# guitar_tuner_main_board.net
KiCad netlist of a schematic drawn in EAGLE
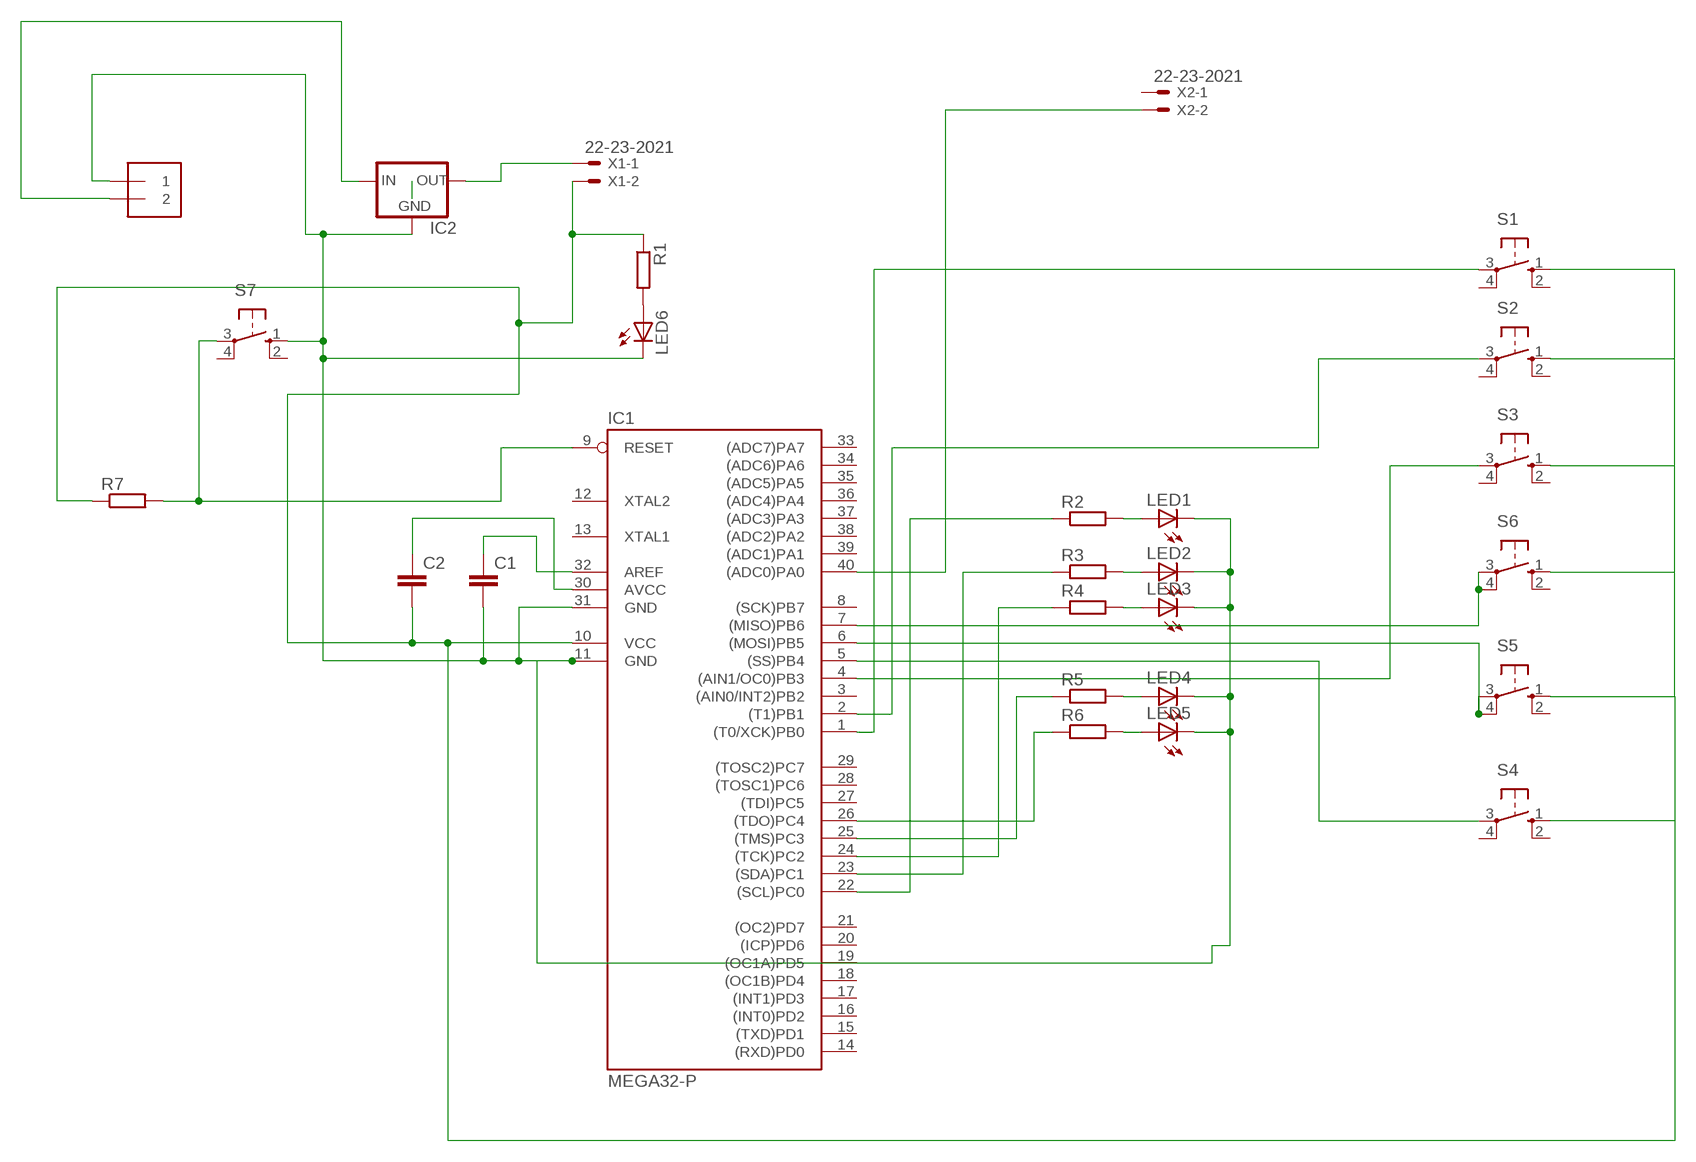
[diagram p0: schematic, sheet 1]

(export (version "E")
  (design (tool "Eeschema 10.0.6"))
  (components
    (comp (ref "C1")
      (value "C-EU025-050X050")
      (footprint "eagle-import:C025-050X050")
      (libsource (lib "eagle-import") (part "C-EU025-050X050"))
    )
    (comp (ref "C2")
      (value "C-EU025-050X050")
      (footprint "eagle-import:C025-050X050")
      (libsource (lib "eagle-import") (part "C-EU025-050X050"))
    )
    (comp (ref "IC1")
      (value "MEGA32-P")
      (footprint "eagle-import:DIL40")
      (fields (field (name "MPN") "ATMEGA32-16PU"))
      (libsource (lib "eagle-import") (part "MEGA32-P"))
    )
    (comp (ref "IC2")
      (value "V_REG_78XX-TO-220")
      (footprint "eagle-import:TO-220-ALT")
      (libsource (lib "eagle-import") (part "V_REG_78XX-TO-220"))
    )
    (comp (ref "J1")
      (value "1X2-3.5MM")
      (footprint "eagle-import:1X2-3.5MM")
      (libsource (lib "eagle-import") (part "1X2-3.5MM"))
    )
    (comp (ref "LED1")
      (value "LED3MM")
      (footprint "eagle-import:LED3MM")
      (libsource (lib "eagle-import") (part "LED3MM"))
    )
    (comp (ref "LED2")
      (value "LED3MM")
      (footprint "eagle-import:LED3MM")
      (libsource (lib "eagle-import") (part "LED3MM"))
    )
    (comp (ref "LED3")
      (value "LED3MM")
      (footprint "eagle-import:LED3MM")
      (libsource (lib "eagle-import") (part "LED3MM"))
    )
    (comp (ref "LED4")
      (value "LED3MM")
      (footprint "eagle-import:LED3MM")
      (libsource (lib "eagle-import") (part "LED3MM"))
    )
    (comp (ref "LED5")
      (value "LED3MM")
      (footprint "eagle-import:LED3MM")
      (libsource (lib "eagle-import") (part "LED3MM"))
    )
    (comp (ref "LED6")
      (value "LED3MM")
      (footprint "eagle-import:LED3MM")
      (libsource (lib "eagle-import") (part "LED3MM"))
    )
    (comp (ref "R1")
      (value "R-EU_0207/7")
      (footprint "eagle-import:0207_7")
      (libsource (lib "eagle-import") (part "R-EU_0207/7"))
    )
    (comp (ref "R2")
      (value "R-EU_0207/7")
      (footprint "eagle-import:0207_7")
      (libsource (lib "eagle-import") (part "R-EU_0207/7"))
    )
    (comp (ref "R3")
      (value "R-EU_0207/7")
      (footprint "eagle-import:0207_7")
      (libsource (lib "eagle-import") (part "R-EU_0207/7"))
    )
    (comp (ref "R4")
      (value "R-EU_0207/7")
      (footprint "eagle-import:0207_7")
      (libsource (lib "eagle-import") (part "R-EU_0207/7"))
    )
    (comp (ref "R5")
      (value "R-EU_0207/7")
      (footprint "eagle-import:0207_7")
      (libsource (lib "eagle-import") (part "R-EU_0207/7"))
    )
    (comp (ref "R6")
      (value "R-EU_0207/7")
      (footprint "eagle-import:0207_7")
      (libsource (lib "eagle-import") (part "R-EU_0207/7"))
    )
    (comp (ref "R7")
      (value "R-EU_0207/7")
      (footprint "eagle-import:0207_7")
      (libsource (lib "eagle-import") (part "R-EU_0207/7"))
    )
    (comp (ref "S1")
      (value "10-XX")
      (footprint "eagle-import:B3F-10XX")
      (fields (field (name "MPN") "B3F-1000"))
      (libsource (lib "eagle-import") (part "10-XX"))
    )
    (comp (ref "S2")
      (value "10-XX")
      (footprint "eagle-import:B3F-10XX")
      (fields (field (name "MPN") "B3F-1000"))
      (libsource (lib "eagle-import") (part "10-XX"))
    )
    (comp (ref "S3")
      (value "10-XX")
      (footprint "eagle-import:B3F-10XX")
      (fields (field (name "MPN") "B3F-1000"))
      (libsource (lib "eagle-import") (part "10-XX"))
    )
    (comp (ref "S4")
      (value "10-XX")
      (footprint "eagle-import:B3F-10XX")
      (fields (field (name "MPN") "B3F-1000"))
      (libsource (lib "eagle-import") (part "10-XX"))
    )
    (comp (ref "S5")
      (value "10-XX")
      (footprint "eagle-import:B3F-10XX")
      (fields (field (name "MPN") "B3F-1000"))
      (libsource (lib "eagle-import") (part "10-XX"))
    )
    (comp (ref "S6")
      (value "10-XX")
      (footprint "eagle-import:B3F-10XX")
      (fields (field (name "MPN") "B3F-1000"))
      (libsource (lib "eagle-import") (part "10-XX"))
    )
    (comp (ref "S7")
      (value "10-XX")
      (footprint "eagle-import:B3F-10XX")
      (fields (field (name "MPN") "B3F-1000"))
      (libsource (lib "eagle-import") (part "10-XX"))
    )
    (comp (ref "X1")
      (value "22-23-2021")
      (footprint "eagle-import:22-23-2021")
      (fields (field (name "MF") "MOLEX"))
      (libsource (lib "eagle-import") (part "22-23-2021"))
    )
    (comp (ref "X2")
      (value "22-23-2021")
      (footprint "eagle-import:22-23-2021")
      (fields (field (name "MF") "MOLEX"))
      (libsource (lib "eagle-import") (part "22-23-2021"))
    )
  )
  (nets
    (net (code "1") (name "Net-(IC1-(ADC0)PA0)") (class "Default")
      (node (ref "IC1") (pin "40") (pinfunction "(ADC0)PA0_40") (pintype "bidirectional"))
      (node (ref "X2") (pin "2") (pinfunction "S_2") (pintype "passive"))
    )
    (net (code "2") (name "Net-(IC1-(AIN1{slash}OC0)PB3)") (class "Default")
      (node (ref "IC1") (pin "4") (pinfunction "(AIN1/OC0)PB3_4") (pintype "bidirectional"))
      (node (ref "S3") (pin "3") (pinfunction "P_3") (pintype "passive"))
    )
    (net (code "3") (name "Net-(IC1-(MISO)PB6)") (class "Default")
      (node (ref "IC1") (pin "7") (pinfunction "(MISO)PB6_7") (pintype "bidirectional"))
      (node (ref "S6") (pin "3") (pinfunction "P_3") (pintype "passive"))
      (node (ref "S6") (pin "4") (pinfunction "P1_4") (pintype "passive"))
    )
    (net (code "4") (name "Net-(IC1-(MOSI)PB5)") (class "Default")
      (node (ref "IC1") (pin "6") (pinfunction "(MOSI)PB5_6") (pintype "bidirectional"))
      (node (ref "S5") (pin "3") (pinfunction "P_3") (pintype "passive"))
      (node (ref "S5") (pin "4") (pinfunction "P1_4") (pintype "passive"))
    )
    (net (code "5") (name "Net-(IC1-(SCL)PC0)") (class "Default")
      (node (ref "IC1") (pin "22") (pinfunction "(SCL)PC0_22") (pintype "bidirectional"))
      (node (ref "R2") (pin "1") (pinfunction "1_1") (pintype "passive"))
    )
    (net (code "6") (name "Net-(IC1-(SDA)PC1)") (class "Default")
      (node (ref "IC1") (pin "23") (pinfunction "(SDA)PC1_23") (pintype "bidirectional"))
      (node (ref "R3") (pin "1") (pinfunction "1_1") (pintype "passive"))
    )
    (net (code "7") (name "Net-(IC1-(SS)PB4)") (class "Default")
      (node (ref "IC1") (pin "5") (pinfunction "(SS)PB4_5") (pintype "bidirectional"))
      (node (ref "S4") (pin "3") (pinfunction "P_3") (pintype "passive"))
    )
    (net (code "8") (name "Net-(IC1-(T0{slash}XCK)PB0)") (class "Default")
      (node (ref "IC1") (pin "1") (pinfunction "(T0/XCK)PB0_1") (pintype "bidirectional"))
      (node (ref "S1") (pin "3") (pinfunction "P_3") (pintype "passive"))
    )
    (net (code "9") (name "Net-(IC1-(T1)PB1)") (class "Default")
      (node (ref "IC1") (pin "2") (pinfunction "(T1)PB1_2") (pintype "bidirectional"))
      (node (ref "S2") (pin "3") (pinfunction "P_3") (pintype "passive"))
    )
    (net (code "10") (name "Net-(IC1-(TCK)PC2)") (class "Default")
      (node (ref "IC1") (pin "24") (pinfunction "(TCK)PC2_24") (pintype "bidirectional"))
      (node (ref "R4") (pin "1") (pinfunction "1_1") (pintype "passive"))
    )
    (net (code "11") (name "Net-(IC1-(TDO)PC4)") (class "Default")
      (node (ref "IC1") (pin "26") (pinfunction "(TDO)PC4_26") (pintype "bidirectional"))
      (node (ref "R6") (pin "1") (pinfunction "1_1") (pintype "passive"))
    )
    (net (code "12") (name "Net-(IC1-(TMS)PC3)") (class "Default")
      (node (ref "IC1") (pin "25") (pinfunction "(TMS)PC3_25") (pintype "bidirectional"))
      (node (ref "R5") (pin "1") (pinfunction "1_1") (pintype "passive"))
    )
    (net (code "13") (name "Net-(IC1-AREF)") (class "Default")
      (node (ref "C1") (pin "1") (pinfunction "1_1") (pintype "passive"))
      (node (ref "IC1") (pin "32") (pinfunction "AREF_32") (pintype "passive"))
    )
    (net (code "14") (name "Net-(IC1-AVCC)") (class "Default")
      (node (ref "C2") (pin "1") (pinfunction "1_1") (pintype "passive"))
      (node (ref "IC1") (pin "30") (pinfunction "AVCC_30") (pintype "power_in"))
    )
    (net (code "15") (name "Net-(IC1-RESET)") (class "Default")
      (node (ref "IC1") (pin "9") (pinfunction "RESET_9") (pintype "input"))
      (node (ref "R7") (pin "2") (pinfunction "2_2") (pintype "passive"))
      (node (ref "S7") (pin "3") (pinfunction "P_3") (pintype "passive"))
    )
    (net (code "16") (name "Net-(IC1-VCC)") (class "Default")
      (node (ref "C2") (pin "2") (pinfunction "2_2") (pintype "passive"))
      (node (ref "IC1") (pin "10") (pinfunction "VCC_10") (pintype "power_in"))
      (node (ref "R1") (pin "1") (pinfunction "1_1") (pintype "passive"))
      (node (ref "R7") (pin "1") (pinfunction "1_1") (pintype "passive"))
      (node (ref "S1") (pin "1") (pinfunction "S_1") (pintype "passive"))
      (node (ref "S2") (pin "1") (pinfunction "S_1") (pintype "passive"))
      (node (ref "S3") (pin "1") (pinfunction "S_1") (pintype "passive"))
      (node (ref "S4") (pin "1") (pinfunction "S_1") (pintype "passive"))
      (node (ref "S5") (pin "1") (pinfunction "S_1") (pintype "passive"))
      (node (ref "S6") (pin "1") (pinfunction "S_1") (pintype "passive"))
      (node (ref "X1") (pin "2") (pinfunction "S_2") (pintype "passive"))
    )
    (net (code "17") (name "Net-(IC2-PadIN)") (class "Default")
      (node (ref "IC2") (pin "IN") (pinfunction "IN_IN") (pintype "input"))
      (node (ref "J1") (pin "2") (pinfunction "2_2") (pintype "passive"))
    )
    (net (code "18") (name "Net-(LED1-C)") (class "Default")
      (node (ref "C1") (pin "2") (pinfunction "2_2") (pintype "passive"))
      (node (ref "IC1") (pin "11") (pinfunction "GND_11") (pintype "power_in"))
      (node (ref "IC1") (pin "31") (pinfunction "GND_31") (pintype "power_in"))
      (node (ref "IC2") (pin "GND") (pinfunction "GND_GND") (pintype "input"))
      (node (ref "J1") (pin "1") (pinfunction "1_1") (pintype "passive"))
      (node (ref "LED1") (pin "K") (pinfunction "C_K") (pintype "passive"))
      (node (ref "LED2") (pin "K") (pinfunction "C_K") (pintype "passive"))
      (node (ref "LED3") (pin "K") (pinfunction "C_K") (pintype "passive"))
      (node (ref "LED4") (pin "K") (pinfunction "C_K") (pintype "passive"))
      (node (ref "LED5") (pin "K") (pinfunction "C_K") (pintype "passive"))
      (node (ref "LED6") (pin "K") (pinfunction "C_K") (pintype "passive"))
      (node (ref "S7") (pin "1") (pinfunction "S_1") (pintype "passive"))
    )
    (net (code "19") (name "Net-(LED1-PadA)") (class "Default")
      (node (ref "LED1") (pin "A") (pinfunction "A_A") (pintype "passive"))
      (node (ref "R2") (pin "2") (pinfunction "2_2") (pintype "passive"))
    )
    (net (code "20") (name "Net-(LED2-PadA)") (class "Default")
      (node (ref "LED2") (pin "A") (pinfunction "A_A") (pintype "passive"))
      (node (ref "R3") (pin "2") (pinfunction "2_2") (pintype "passive"))
    )
    (net (code "21") (name "Net-(LED3-PadA)") (class "Default")
      (node (ref "LED3") (pin "A") (pinfunction "A_A") (pintype "passive"))
      (node (ref "R4") (pin "2") (pinfunction "2_2") (pintype "passive"))
    )
    (net (code "22") (name "Net-(LED4-PadA)") (class "Default")
      (node (ref "LED4") (pin "A") (pinfunction "A_A") (pintype "passive"))
      (node (ref "R5") (pin "2") (pinfunction "2_2") (pintype "passive"))
    )
    (net (code "23") (name "Net-(LED5-PadA)") (class "Default")
      (node (ref "LED5") (pin "A") (pinfunction "A_A") (pintype "passive"))
      (node (ref "R6") (pin "2") (pinfunction "2_2") (pintype "passive"))
    )
    (net (code "24") (name "Net-(LED6-PadA)") (class "Default")
      (node (ref "LED6") (pin "A") (pinfunction "A_A") (pintype "passive"))
      (node (ref "R1") (pin "2") (pinfunction "2_2") (pintype "passive"))
    )
    (net (code "25") (name "Net-(X1A-S)") (class "Default")
      (node (ref "IC2") (pin "OUT") (pinfunction "OUT_OUT") (pintype "output"))
      (node (ref "X1") (pin "1") (pinfunction "S_1") (pintype "passive"))
    )
    (net (code "26") (name "unconnected-(IC1-(ADC1)PA1-Pad39)") (class "Default")
      (node (ref "IC1") (pin "39") (pinfunction "(ADC1)PA1_39") (pintype "bidirectional"))
    )
    (net (code "27") (name "unconnected-(IC1-(ADC2)PA2-Pad38)") (class "Default")
      (node (ref "IC1") (pin "38") (pinfunction "(ADC2)PA2_38") (pintype "bidirectional"))
    )
    (net (code "28") (name "unconnected-(IC1-(ADC3)PA3-Pad37)") (class "Default")
      (node (ref "IC1") (pin "37") (pinfunction "(ADC3)PA3_37") (pintype "bidirectional"))
    )
    (net (code "29") (name "unconnected-(IC1-(ADC4)PA4-Pad36)") (class "Default")
      (node (ref "IC1") (pin "36") (pinfunction "(ADC4)PA4_36") (pintype "bidirectional"))
    )
    (net (code "30") (name "unconnected-(IC1-(ADC5)PA5-Pad35)") (class "Default")
      (node (ref "IC1") (pin "35") (pinfunction "(ADC5)PA5_35") (pintype "bidirectional"))
    )
    (net (code "31") (name "unconnected-(IC1-(ADC6)PA6-Pad34)") (class "Default")
      (node (ref "IC1") (pin "34") (pinfunction "(ADC6)PA6_34") (pintype "bidirectional"))
    )
    (net (code "32") (name "unconnected-(IC1-(ADC7)PA7-Pad33)") (class "Default")
      (node (ref "IC1") (pin "33") (pinfunction "(ADC7)PA7_33") (pintype "bidirectional"))
    )
    (net (code "33") (name "unconnected-(IC1-(AIN0{slash}INT2)PB2-Pad3)") (class "Default")
      (node (ref "IC1") (pin "3") (pinfunction "(AIN0/INT2)PB2_3") (pintype "bidirectional"))
    )
    (net (code "34") (name "unconnected-(IC1-(ICP)PD6-Pad20)") (class "Default")
      (node (ref "IC1") (pin "20") (pinfunction "(ICP)PD6_20") (pintype "bidirectional"))
    )
    (net (code "35") (name "unconnected-(IC1-(INT0)PD2-Pad16)") (class "Default")
      (node (ref "IC1") (pin "16") (pinfunction "(INT0)PD2_16") (pintype "bidirectional"))
    )
    (net (code "36") (name "unconnected-(IC1-(INT1)PD3-Pad17)") (class "Default")
      (node (ref "IC1") (pin "17") (pinfunction "(INT1)PD3_17") (pintype "bidirectional"))
    )
    (net (code "37") (name "unconnected-(IC1-(OC1A)PD5-Pad19)") (class "Default")
      (node (ref "IC1") (pin "19") (pinfunction "(OC1A)PD5_19") (pintype "bidirectional"))
    )
    (net (code "38") (name "unconnected-(IC1-(OC1B)PD4-Pad18)") (class "Default")
      (node (ref "IC1") (pin "18") (pinfunction "(OC1B)PD4_18") (pintype "bidirectional"))
    )
    (net (code "39") (name "unconnected-(IC1-(OC2)PD7-Pad21)") (class "Default")
      (node (ref "IC1") (pin "21") (pinfunction "(OC2)PD7_21") (pintype "bidirectional"))
    )
    (net (code "40") (name "unconnected-(IC1-(RXD)PD0-Pad14)") (class "Default")
      (node (ref "IC1") (pin "14") (pinfunction "(RXD)PD0_14") (pintype "bidirectional"))
    )
    (net (code "41") (name "unconnected-(IC1-(SCK)PB7-Pad8)") (class "Default")
      (node (ref "IC1") (pin "8") (pinfunction "(SCK)PB7_8") (pintype "bidirectional"))
    )
    (net (code "42") (name "unconnected-(IC1-(TDI)PC5-Pad27)") (class "Default")
      (node (ref "IC1") (pin "27") (pinfunction "(TDI)PC5_27") (pintype "bidirectional"))
    )
    (net (code "43") (name "unconnected-(IC1-(TOSC1)PC6-Pad28)") (class "Default")
      (node (ref "IC1") (pin "28") (pinfunction "(TOSC1)PC6_28") (pintype "bidirectional"))
    )
    (net (code "44") (name "unconnected-(IC1-(TOSC2)PC7-Pad29)") (class "Default")
      (node (ref "IC1") (pin "29") (pinfunction "(TOSC2)PC7_29") (pintype "bidirectional"))
    )
    (net (code "45") (name "unconnected-(IC1-(TXD)PD1-Pad15)") (class "Default")
      (node (ref "IC1") (pin "15") (pinfunction "(TXD)PD1_15") (pintype "bidirectional"))
    )
    (net (code "46") (name "unconnected-(IC1-XTAL1-Pad13)") (class "Default")
      (node (ref "IC1") (pin "13") (pinfunction "XTAL1_13") (pintype "bidirectional"))
    )
    (net (code "47") (name "unconnected-(IC1-XTAL2-Pad12)") (class "Default")
      (node (ref "IC1") (pin "12") (pinfunction "XTAL2_12") (pintype "bidirectional"))
    )
    (net (code "48") (name "unconnected-(S1-P1-Pad4)") (class "Default")
      (node (ref "S1") (pin "4") (pinfunction "P1_4") (pintype "passive"))
    )
    (net (code "49") (name "unconnected-(S1-S1-Pad2)") (class "Default")
      (node (ref "S1") (pin "2") (pinfunction "S1_2") (pintype "passive"))
    )
    (net (code "50") (name "unconnected-(S2-P1-Pad4)") (class "Default")
      (node (ref "S2") (pin "4") (pinfunction "P1_4") (pintype "passive"))
    )
    (net (code "51") (name "unconnected-(S2-S1-Pad2)") (class "Default")
      (node (ref "S2") (pin "2") (pinfunction "S1_2") (pintype "passive"))
    )
    (net (code "52") (name "unconnected-(S3-P1-Pad4)") (class "Default")
      (node (ref "S3") (pin "4") (pinfunction "P1_4") (pintype "passive"))
    )
    (net (code "53") (name "unconnected-(S3-S1-Pad2)") (class "Default")
      (node (ref "S3") (pin "2") (pinfunction "S1_2") (pintype "passive"))
    )
    (net (code "54") (name "unconnected-(S4-P1-Pad4)") (class "Default")
      (node (ref "S4") (pin "4") (pinfunction "P1_4") (pintype "passive"))
    )
    (net (code "55") (name "unconnected-(S4-S1-Pad2)") (class "Default")
      (node (ref "S4") (pin "2") (pinfunction "S1_2") (pintype "passive"))
    )
    (net (code "56") (name "unconnected-(S5-S1-Pad2)") (class "Default")
      (node (ref "S5") (pin "2") (pinfunction "S1_2") (pintype "passive"))
    )
    (net (code "57") (name "unconnected-(S6-S1-Pad2)") (class "Default")
      (node (ref "S6") (pin "2") (pinfunction "S1_2") (pintype "passive"))
    )
    (net (code "58") (name "unconnected-(S7-P1-Pad4)") (class "Default")
      (node (ref "S7") (pin "4") (pinfunction "P1_4") (pintype "passive"))
    )
    (net (code "59") (name "unconnected-(S7-S1-Pad2)") (class "Default")
      (node (ref "S7") (pin "2") (pinfunction "S1_2") (pintype "passive"))
    )
    (net (code "60") (name "unconnected-(X2A-S-Pad1)") (class "Default")
      (node (ref "X2") (pin "1") (pinfunction "S_1") (pintype "passive"))
    )
  )
)
